# electrical_diagram.net
KiCad netlist of a schematic drawn in EAGLE
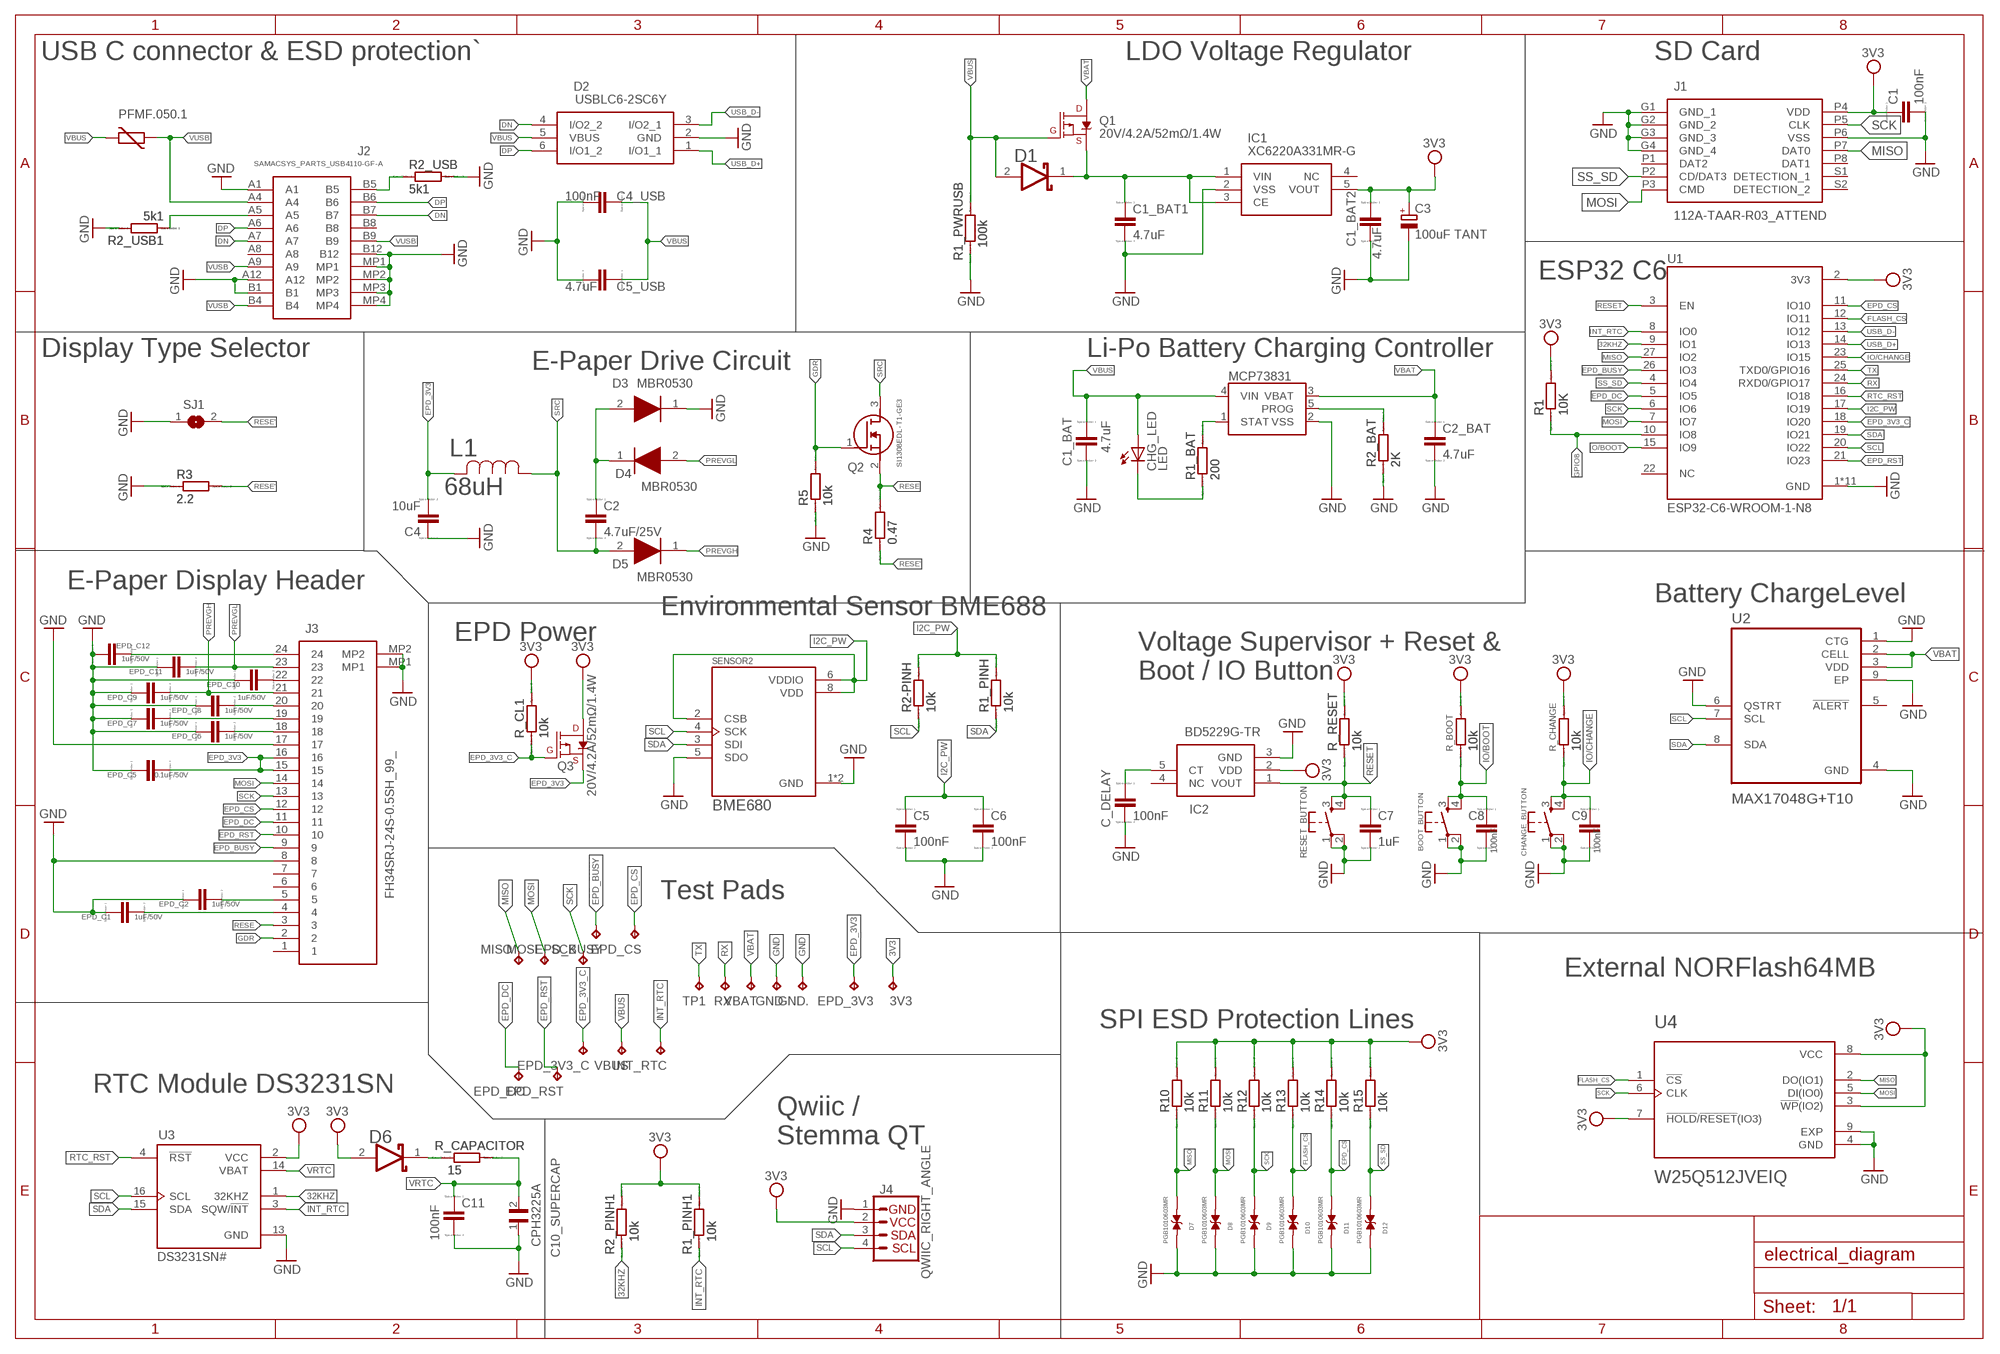
[diagram p0: schematic, sheet 1]

(export (version "E")
  (design (tool "Eeschema 10.0.6"))
  (components
    (comp (ref "3V3")
      (value "TP")
      (footprint "eagle-import:TP20R")
      (libsource (lib "eagle-import") (part "TP"))
    )
    (comp (ref "BOOT_BUTTON")
      (value "BUTTON_CUSYOMV1")
      (footprint "eagle-import:MYBUTTON")
      (libsource (lib "eagle-import") (part "BUTTON_CUSYOMV1"))
    )
    (comp (ref "C1")
      (value "100nF")
      (footprint "eagle-import:EAGLE-LTSPICE_C0402")
      (libsource (lib "eagle-import") (part "EAGLE-LTSPICE_C"))
    )
    (comp (ref "C1_BAT")
      (value "4.7uF")
      (footprint "eagle-import:EAGLE-LTSPICE_C0402")
      (libsource (lib "eagle-import") (part "EAGLE-LTSPICE_C"))
    )
    (comp (ref "C1_BAT1")
      (value "4.7uF")
      (footprint "eagle-import:EAGLE-LTSPICE_C0402")
      (libsource (lib "eagle-import") (part "EAGLE-LTSPICE_C"))
    )
    (comp (ref "C1_BAT2")
      (value "4.7uF")
      (footprint "eagle-import:EAGLE-LTSPICE_C0402")
      (libsource (lib "eagle-import") (part "EAGLE-LTSPICE_C"))
    )
    (comp (ref "C2")
      (value "4.7uF/25V")
      (footprint "eagle-import:EAGLE-LTSPICE_C0402")
      (libsource (lib "eagle-import") (part "EAGLE-LTSPICE_C"))
    )
    (comp (ref "C2_BAT")
      (value "4.7uF")
      (footprint "eagle-import:EAGLE-LTSPICE_C0402")
      (libsource (lib "eagle-import") (part "EAGLE-LTSPICE_C"))
    )
    (comp (ref "C3")
      (value "100uF TANT")
      (footprint "eagle-import:RCL_CT3528")
      (libsource (lib "eagle-import") (part "RCL_CPOL-EUCT3528"))
    )
    (comp (ref "C4")
      (value "10uF")
      (footprint "eagle-import:EAGLE-LTSPICE_C0402")
      (libsource (lib "eagle-import") (part "EAGLE-LTSPICE_C"))
    )
    (comp (ref "C4_USB")
      (value "100nF")
      (footprint "eagle-import:EAGLE-LTSPICE_C0402")
      (libsource (lib "eagle-import") (part "EAGLE-LTSPICE_C"))
    )
    (comp (ref "C5")
      (value "100nF")
      (footprint "eagle-import:ESP32_WROVER_EAGLE-LTSPICE_C0402")
      (libsource (lib "eagle-import") (part "ESP32_WROVER_EAGLE-LTSPICE_CC0402"))
    )
    (comp (ref "C5_USB")
      (value "4.7uF")
      (footprint "eagle-import:EAGLE-LTSPICE_C0402")
      (libsource (lib "eagle-import") (part "EAGLE-LTSPICE_C"))
    )
    (comp (ref "C6")
      (value "100nF")
      (footprint "eagle-import:ESP32_WROVER_EAGLE-LTSPICE_C0402")
      (libsource (lib "eagle-import") (part "ESP32_WROVER_EAGLE-LTSPICE_CC0402"))
    )
    (comp (ref "C7")
      (value "1uF")
      (footprint "eagle-import:ESP32_WROVER_EAGLE-LTSPICE_C0402")
      (libsource (lib "eagle-import") (part "ESP32_WROVER_EAGLE-LTSPICE_CC0402"))
    )
    (comp (ref "C8")
      (value "100nF")
      (footprint "eagle-import:ESP32_WROVER_EAGLE-LTSPICE_C0402")
      (libsource (lib "eagle-import") (part "ESP32_WROVER_EAGLE-LTSPICE_CC0402"))
    )
    (comp (ref "C9")
      (value "100nF")
      (footprint "eagle-import:ESP32_WROVER_EAGLE-LTSPICE_C0402")
      (libsource (lib "eagle-import") (part "ESP32_WROVER_EAGLE-LTSPICE_CC0402"))
    )
    (comp (ref "C10_SUPERCAP")
      (value "CPH3225A")
      (footprint "eagle-import:CAPCP3225X100N")
      (fields (field (name "MF") "Seiko Instruments"))
      (libsource (lib "eagle-import") (part "CPH3225A"))
    )
    (comp (ref "C11")
      (value "100nF")
      (footprint "eagle-import:ESP32_WROVER_EAGLE-LTSPICE_C0402")
      (libsource (lib "eagle-import") (part "ESP32_WROVER_EAGLE-LTSPICE_CC0402"))
    )
    (comp (ref "CHANGE_BUTTON")
      (value "BUTTON_CUSYOMV1")
      (footprint "eagle-import:MYBUTTON")
      (libsource (lib "eagle-import") (part "BUTTON_CUSYOMV1"))
    )
    (comp (ref "CHG_LED")
      (value "LED")
      (footprint "eagle-import:ADAFRUIT_CHIP-LED0603")
      (libsource (lib "eagle-import") (part "ADAFRUIT_LEDCHIP-LED0603"))
    )
    (comp (ref "C_DELAY")
      (value "100nF")
      (footprint "eagle-import:ESP32_WROVER_EAGLE-LTSPICE_C0402")
      (libsource (lib "eagle-import") (part "ESP32_WROVER_EAGLE-LTSPICE_CC0402"))
    )
    (comp (ref "D1")
      (value "ESP32_WROVER_AVX---SD0805S020S1R0_AVX_SD0805S020S1R0_0_0AVX_SD0805S020S1R0_0_0")
      (footprint "eagle-import:ESP32_WROVER_AVX---SD0805S020S1R0_AVX_SD0805S020S1R0_0")
      (fields
        (field (name "DIGIKEY_PART_NUMBER") "478-7800-1-ND")
        (field (name "MF") "AVX")
        (field (name "MOUSER_PART_NUMBER") "581-SD0805S020S1R0")
      )
      (libsource (lib "eagle-import") (part "ESP32_WROVER_AVX---SD0805S020S1R0_AVX_SD0805S020S1R0_0_0AVX_SD0805S020S1R0_0_0"))
    )
    (comp (ref "D2")
      (value "USBLC6-2SC6Y")
      (footprint "eagle-import:SOT95P280X145-6N")
      (fields (field (name "MF") "STMicroelectronics"))
      (libsource (lib "eagle-import") (part "USBLC6-2SC6Y"))
    )
    (comp (ref "D3")
      (value "MBR0530")
      (footprint "eagle-import:SOD3716X135N")
      (fields (field (name "MF") "ON Semiconductor"))
      (libsource (lib "eagle-import") (part "MBR0530"))
    )
    (comp (ref "D4")
      (value "MBR0530")
      (footprint "eagle-import:SOD3716X135N")
      (fields (field (name "MF") "ON Semiconductor"))
      (libsource (lib "eagle-import") (part "MBR0530"))
    )
    (comp (ref "D5")
      (value "MBR0530")
      (footprint "eagle-import:SOD3716X135N")
      (fields (field (name "MF") "ON Semiconductor"))
      (libsource (lib "eagle-import") (part "MBR0530"))
    )
    (comp (ref "D6")
      (value "ESP32_WROVER_AVX---SD0805S020S1R0_AVX_SD0805S020S1R0_0_0AVX_SD0805S020S1R0_0_0")
      (footprint "eagle-import:ESP32_WROVER_AVX---SD0805S020S1R0_AVX_SD0805S020S1R0_0")
      (fields
        (field (name "DIGIKEY_PART_NUMBER") "478-7800-1-ND")
        (field (name "MF") "AVX")
        (field (name "MOUSER_PART_NUMBER") "581-SD0805S020S1R0")
      )
      (libsource (lib "eagle-import") (part "ESP32_WROVER_AVX---SD0805S020S1R0_AVX_SD0805S020S1R0_0_0AVX_SD0805S020S1R0_0_0"))
    )
    (comp (ref "D7")
      (value "PGB1010603MR")
      (footprint "eagle-import:DIOC1608X36N")
      (fields (field (name "MF") "Littelfuse Inc."))
      (libsource (lib "eagle-import") (part "PGB1010603MR"))
    )
    (comp (ref "D8")
      (value "PGB1010603MR")
      (footprint "eagle-import:DIOC1608X36N")
      (fields (field (name "MF") "Littelfuse Inc."))
      (libsource (lib "eagle-import") (part "PGB1010603MR"))
    )
    (comp (ref "D9")
      (value "PGB1010603MR")
      (footprint "eagle-import:DIOC1608X36N")
      (fields (field (name "MF") "Littelfuse Inc."))
      (libsource (lib "eagle-import") (part "PGB1010603MR"))
    )
    (comp (ref "D10")
      (value "PGB1010603MR")
      (footprint "eagle-import:DIOC1608X36N")
      (fields (field (name "MF") "Littelfuse Inc."))
      (libsource (lib "eagle-import") (part "PGB1010603MR"))
    )
    (comp (ref "D11")
      (value "PGB1010603MR")
      (footprint "eagle-import:DIOC1608X36N")
      (fields (field (name "MF") "Littelfuse Inc."))
      (libsource (lib "eagle-import") (part "PGB1010603MR"))
    )
    (comp (ref "D12")
      (value "PGB1010603MR")
      (footprint "eagle-import:DIOC1608X36N")
      (fields (field (name "MF") "Littelfuse Inc."))
      (libsource (lib "eagle-import") (part "PGB1010603MR"))
    )
    (comp (ref "EPD_3V3")
      (value "TP")
      (footprint "eagle-import:TP20R")
      (libsource (lib "eagle-import") (part "TP"))
    )
    (comp (ref "EPD_3V3_C")
      (value "TP")
      (footprint "eagle-import:TP20R")
      (libsource (lib "eagle-import") (part "TP"))
    )
    (comp (ref "EPD_BUSY")
      (value "TP")
      (footprint "eagle-import:TP20R")
      (libsource (lib "eagle-import") (part "TP"))
    )
    (comp (ref "EPD_C1")
      (value "1uF/50V")
      (footprint "eagle-import:EAGLE-LTSPICE_C0402")
      (libsource (lib "eagle-import") (part "EAGLE-LTSPICE_C"))
    )
    (comp (ref "EPD_C2")
      (value "1uF/50V")
      (footprint "eagle-import:EAGLE-LTSPICE_C0402")
      (libsource (lib "eagle-import") (part "EAGLE-LTSPICE_C"))
    )
    (comp (ref "EPD_C5")
      (value "0.1uF/50V")
      (footprint "eagle-import:EAGLE-LTSPICE_C0402")
      (libsource (lib "eagle-import") (part "EAGLE-LTSPICE_C"))
    )
    (comp (ref "EPD_C6")
      (value "1uF/50V")
      (footprint "eagle-import:EAGLE-LTSPICE_C0402")
      (libsource (lib "eagle-import") (part "EAGLE-LTSPICE_C"))
    )
    (comp (ref "EPD_C7")
      (value "1uF/50V")
      (footprint "eagle-import:EAGLE-LTSPICE_C0402")
      (libsource (lib "eagle-import") (part "EAGLE-LTSPICE_C"))
    )
    (comp (ref "EPD_C8")
      (value "1uF/50V")
      (footprint "eagle-import:EAGLE-LTSPICE_C0402")
      (libsource (lib "eagle-import") (part "EAGLE-LTSPICE_C"))
    )
    (comp (ref "EPD_C9")
      (value "1uF/50V")
      (footprint "eagle-import:EAGLE-LTSPICE_C0402")
      (libsource (lib "eagle-import") (part "EAGLE-LTSPICE_C"))
    )
    (comp (ref "EPD_C10")
      (value "1uF/50V")
      (footprint "eagle-import:EAGLE-LTSPICE_C0402")
      (libsource (lib "eagle-import") (part "EAGLE-LTSPICE_C"))
    )
    (comp (ref "EPD_C11")
      (value "1uF/50V")
      (footprint "eagle-import:EAGLE-LTSPICE_C0402")
      (libsource (lib "eagle-import") (part "EAGLE-LTSPICE_C"))
    )
    (comp (ref "EPD_C12")
      (value "1uF/50V")
      (footprint "eagle-import:EAGLE-LTSPICE_C0402")
      (libsource (lib "eagle-import") (part "EAGLE-LTSPICE_C"))
    )
    (comp (ref "EPD_CS")
      (value "TP")
      (footprint "eagle-import:TP20R")
      (libsource (lib "eagle-import") (part "TP"))
    )
    (comp (ref "EPD_DC")
      (value "TP")
      (footprint "eagle-import:TP20R")
      (libsource (lib "eagle-import") (part "TP"))
    )
    (comp (ref "EPD_RST")
      (value "TP")
      (footprint "eagle-import:TP20R")
      (libsource (lib "eagle-import") (part "TP"))
    )
    (comp (ref "GND")
      (value "TP")
      (footprint "eagle-import:TP20R")
      (libsource (lib "eagle-import") (part "TP"))
    )
    (comp (ref "GND.")
      (value "TP")
      (footprint "eagle-import:TP20R")
      (libsource (lib "eagle-import") (part "TP"))
    )
    (comp (ref "IC1")
      (value "XC6220A331MR-G")
      (footprint "eagle-import:SOT95P280X120-5N")
      (fields (field (name "MOUSER_PART_NUMBER") "865-XC6220A331MR-G"))
      (libsource (lib "eagle-import") (part "XC6220A331MR-G"))
    )
    (comp (ref "IC2")
      (value "BD5229G-TR")
      (footprint "eagle-import:SOT95P280X125-5N")
      (fields (field (name "MOUSER_PART_NUMBER") "755-BD5229G-TR"))
      (libsource (lib "eagle-import") (part "BD5229G-TR"))
    )
    (comp (ref "INT_RTC")
      (value "TP")
      (footprint "eagle-import:TP20R")
      (libsource (lib "eagle-import") (part "TP"))
    )
    (comp (ref "J1")
      (value "112A-TAAR-R03_ATTEND")
      (footprint "eagle-import:112ATAARR03ATTEND")
      (fields (field (name "MANUFACTURER_PART_NUMBER") "112A-TAAR-R03 ATTEND"))
      (libsource (lib "eagle-import") (part "112A-TAAR-R03_ATTEND"))
    )
    (comp (ref "J2")
      (value "SAMACSYS_PARTS_USB4110-GF-A")
      (footprint "eagle-import:SAMACSYS_PARTS_USB4110GFA")
      (fields
        (field (name "MANUFACTURER_PART_NUMBER") "USB4110-GF-A")
        (field (name "MOUSER_PART_NUMBER") "640-USB4110-GF-A")
      )
      (libsource (lib "eagle-import") (part "SAMACSYS_PARTS_USB4110-GF-A"))
    )
    (comp (ref "J3")
      (value "FH34SRJ-24S-0.5SH_99_")
      (footprint "eagle-import:FH34SRJ24S05SH99")
      (fields
        (field (name "MANUFACTURER_PART_NUMBER") "FH34SRJ-24S-0.5SH(99)")
        (field (name "MOUSER_PART_NUMBER") "798-FH34SRJ24S05SH99")
      )
      (libsource (lib "eagle-import") (part "FH34SRJ-24S-0.5SH_99_"))
    )
    (comp (ref "J4")
      (value "QWIIC_RIGHT_ANGLE")
      (footprint "eagle-import:JST04_1MM_RA")
      (libsource (lib "eagle-import") (part "QWIIC_CONNECTORJS-1MM"))
    )
    (comp (ref "L1")
      (value "68uH")
      (footprint "eagle-import:IND_4828-WE-TPC_WRE")
      (fields
        (field (name "MANUFACTURER_PART_NUMBER") "744043680")
        (field (name "COPYRIGHT") "Copyright (C) 2024 Ultra Librarian. All rights reserved.")
      )
      (libsource (lib "eagle-import") (part "744043680IND_4828-WE-TPC_WRE"))
    )
    (comp (ref "MCP73831")
      (value "ESP32_WROVER_SPARKFUN-IC-POWER_MCP73831")
      (footprint "eagle-import:ESP32_WROVER_SPARKFUN-IC-POWER_SOT23-5")
      (libsource (lib "eagle-import") (part "ESP32_WROVER_SPARKFUN-IC-POWER_MCP73831"))
    )
    (comp (ref "MISO")
      (value "TP")
      (footprint "eagle-import:TP20R")
      (libsource (lib "eagle-import") (part "TP"))
    )
    (comp (ref "MOSI")
      (value "TP")
      (footprint "eagle-import:TP20R")
      (libsource (lib "eagle-import") (part "TP"))
    )
    (comp (ref "PFMF.050.1")
      (value "ESP32C6_VARISTORCN1812")
      (footprint "eagle-import:ESP32C6_VARISTOR_CT_CN1812")
      (libsource (lib "eagle-import") (part "ESP32C6_VARISTORCN1812"))
    )
    (comp (ref "Q1")
      (value "20V/4.2A/52mΩ/1.4W")
      (footprint "eagle-import:ESP32_WROVER_SPARKFUN-DISCRETESEMI_SOT23-3")
      (libsource (lib "eagle-import") (part "ESP32_WROVER_SPARKFUN-DISCRETESEMI_MOSFET_PCH-DMG2305UX-7"))
    )
    (comp (ref "Q2")
      (value "SI1308EDL-T1-GE3")
      (footprint "eagle-import:SOT65P210X110-3N")
      (fields (field (name "MF") "Vishay Siliconix"))
      (libsource (lib "eagle-import") (part "SI1308EDL-T1-GE3"))
    )
    (comp (ref "Q3")
      (value "20V/4.2A/52mΩ/1.4W")
      (footprint "eagle-import:ESP32_WROVER_SPARKFUN-DISCRETESEMI_SOT23-3")
      (libsource (lib "eagle-import") (part "ESP32_WROVER_SPARKFUN-DISCRETESEMI_MOSFET_PCH-DMG2305UX-7"))
    )
    (comp (ref "R1")
      (value "10K")
      (footprint "eagle-import:ESP32_WROVER_EAGLE-LTSPICE_R0402")
      (libsource (lib "eagle-import") (part "ESP32_WROVER_EAGLE-LTSPICE_R"))
    )
    (comp (ref "R1_BAT")
      (value "200")
      (footprint "eagle-import:ESP32_WROVER_EAGLE-LTSPICE_R0402")
      (libsource (lib "eagle-import") (part "ESP32_WROVER_EAGLE-LTSPICE_R"))
    )
    (comp (ref "R1_PINH")
      (value "10k")
      (footprint "eagle-import:ESP32_WROVER_EAGLE-LTSPICE_R0402")
      (libsource (lib "eagle-import") (part "ESP32_WROVER_EAGLE-LTSPICE_R"))
    )
    (comp (ref "R1_PINH1")
      (value "10k")
      (footprint "eagle-import:ESP32_WROVER_EAGLE-LTSPICE_R0402")
      (libsource (lib "eagle-import") (part "ESP32_WROVER_EAGLE-LTSPICE_R"))
    )
    (comp (ref "R1_PWRUSB")
      (value "100k")
      (footprint "eagle-import:ESP32_WROVER_EAGLE-LTSPICE_R0402")
      (libsource (lib "eagle-import") (part "ESP32_WROVER_EAGLE-LTSPICE_R"))
    )
    (comp (ref "R2-PINH")
      (value "10k")
      (footprint "eagle-import:ESP32_WROVER_EAGLE-LTSPICE_R0402")
      (libsource (lib "eagle-import") (part "ESP32_WROVER_EAGLE-LTSPICE_R"))
    )
    (comp (ref "R2_BAT")
      (value "2K")
      (footprint "eagle-import:ESP32_WROVER_EAGLE-LTSPICE_R0402")
      (libsource (lib "eagle-import") (part "ESP32_WROVER_EAGLE-LTSPICE_R"))
    )
    (comp (ref "R2_PINH1")
      (value "10k")
      (footprint "eagle-import:ESP32_WROVER_EAGLE-LTSPICE_R0402")
      (libsource (lib "eagle-import") (part "ESP32_WROVER_EAGLE-LTSPICE_R"))
    )
    (comp (ref "R2_USB")
      (value "5k1")
      (footprint "eagle-import:ESP32_WROVER_EAGLE-LTSPICE_R0402")
      (libsource (lib "eagle-import") (part "ESP32_WROVER_EAGLE-LTSPICE_R"))
    )
    (comp (ref "R2_USB1")
      (value "5k1")
      (footprint "eagle-import:ESP32_WROVER_EAGLE-LTSPICE_R0402")
      (libsource (lib "eagle-import") (part "ESP32_WROVER_EAGLE-LTSPICE_R"))
    )
    (comp (ref "R3")
      (value "2.2")
      (footprint "eagle-import:ESP32_WROVER_EAGLE-LTSPICE_R0402")
      (libsource (lib "eagle-import") (part "ESP32_WROVER_EAGLE-LTSPICE_R"))
    )
    (comp (ref "R4")
      (value "0.47")
      (footprint "eagle-import:ESP32_WROVER_EAGLE-LTSPICE_R0402")
      (libsource (lib "eagle-import") (part "ESP32_WROVER_EAGLE-LTSPICE_R"))
    )
    (comp (ref "R5")
      (value "10k")
      (footprint "eagle-import:ESP32_WROVER_EAGLE-LTSPICE_R0402")
      (libsource (lib "eagle-import") (part "ESP32_WROVER_EAGLE-LTSPICE_R"))
    )
    (comp (ref "R10")
      (value "10k")
      (footprint "eagle-import:ESP32_WROVER_EAGLE-LTSPICE_R0402")
      (libsource (lib "eagle-import") (part "ESP32_WROVER_EAGLE-LTSPICE_R"))
    )
    (comp (ref "R11")
      (value "10k")
      (footprint "eagle-import:ESP32_WROVER_EAGLE-LTSPICE_R0402")
      (libsource (lib "eagle-import") (part "ESP32_WROVER_EAGLE-LTSPICE_R"))
    )
    (comp (ref "R12")
      (value "10k")
      (footprint "eagle-import:ESP32_WROVER_EAGLE-LTSPICE_R0402")
      (libsource (lib "eagle-import") (part "ESP32_WROVER_EAGLE-LTSPICE_R"))
    )
    (comp (ref "R13")
      (value "10k")
      (footprint "eagle-import:ESP32_WROVER_EAGLE-LTSPICE_R0402")
      (libsource (lib "eagle-import") (part "ESP32_WROVER_EAGLE-LTSPICE_R"))
    )
    (comp (ref "R14")
      (value "10k")
      (footprint "eagle-import:ESP32_WROVER_EAGLE-LTSPICE_R0402")
      (libsource (lib "eagle-import") (part "ESP32_WROVER_EAGLE-LTSPICE_R"))
    )
    (comp (ref "R15")
      (value "10k")
      (footprint "eagle-import:ESP32_WROVER_EAGLE-LTSPICE_R0402")
      (libsource (lib "eagle-import") (part "ESP32_WROVER_EAGLE-LTSPICE_R"))
    )
    (comp (ref "RESET_BUTTON")
      (value "BUTTON_CUSYOMV1")
      (footprint "eagle-import:MYBUTTON")
      (libsource (lib "eagle-import") (part "BUTTON_CUSYOMV1"))
    )
    (comp (ref "RX")
      (value "TP")
      (footprint "eagle-import:TP20R")
      (libsource (lib "eagle-import") (part "TP"))
    )
    (comp (ref "R_BOOT")
      (value "10k")
      (footprint "eagle-import:ESP32_WROVER_EAGLE-LTSPICE_R0402")
      (libsource (lib "eagle-import") (part "ESP32_WROVER_EAGLE-LTSPICE_R"))
    )
    (comp (ref "R_CAPACITOR")
      (value "15")
      (footprint "eagle-import:ESP32_WROVER_EAGLE-LTSPICE_R0402")
      (libsource (lib "eagle-import") (part "ESP32_WROVER_EAGLE-LTSPICE_R"))
    )
    (comp (ref "R_CHANGE")
      (value "10k")
      (footprint "eagle-import:ESP32_WROVER_EAGLE-LTSPICE_R0402")
      (libsource (lib "eagle-import") (part "ESP32_WROVER_EAGLE-LTSPICE_R"))
    )
    (comp (ref "R_CL1")
      (value "10k")
      (footprint "eagle-import:ESP32_WROVER_EAGLE-LTSPICE_R0402")
      (libsource (lib "eagle-import") (part "ESP32_WROVER_EAGLE-LTSPICE_R"))
    )
    (comp (ref "R_RESET")
      (value "10k")
      (footprint "eagle-import:ESP32_WROVER_EAGLE-LTSPICE_R0402")
      (libsource (lib "eagle-import") (part "ESP32_WROVER_EAGLE-LTSPICE_R"))
    )
    (comp (ref "SCK")
      (value "TP")
      (footprint "eagle-import:TP20R")
      (libsource (lib "eagle-import") (part "TP"))
    )
    (comp (ref "SENSOR2")
      (value "BME680")
      (footprint "eagle-import:ESP32_WROVER_BME680_PSON80P300X300X100-8N")
      (fields (field (name "MF") "Bosch Sensortec"))
      (libsource (lib "eagle-import") (part "ESP32_WROVER_BME680_BME680"))
    )
    (comp (ref "SJ1") (value "-") (footprint "eagle-import:SJ") (libsource (lib "eagle-import") (part "SJ")))
    (comp (ref "TP1")
      (value "TP")
      (footprint "eagle-import:TP20R")
      (libsource (lib "eagle-import") (part "TP"))
    )
    (comp (ref "U1")
      (value "ESP32-C6-WROOM-1-N8")
      (footprint "eagle-import:XCVR_ESP32-C6-WROOM-1-N8")
      (fields (field (name "MF") "Espressif Systems"))
      (libsource (lib "eagle-import") (part "ESP32-C6-WROOM-1-N8"))
    )
    (comp (ref "U2")
      (value "MAX17048G+T10")
      (footprint "eagle-import:SON50P200X200X80-9N")
      (fields (field (name "MF") "Analog Devices"))
      (libsource (lib "eagle-import") (part "MAX17048G+T10"))
    )
    (comp (ref "U3")
      (value "DS3231SN#")
      (footprint "eagle-import:SOIC127P1032X265-16N")
      (fields (field (name "MF") "Analog Devices"))
      (libsource (lib "eagle-import") (part "DS3231SN#"))
    )
    (comp (ref "U4")
      (value "W25Q512JVEIQ")
      (footprint "eagle-import:SON127P600X800X80-9N")
      (fields (field (name "MF") "Winbond Electronics"))
      (libsource (lib "eagle-import") (part "W25Q512JVEIQ"))
    )
    (comp (ref "VBAT")
      (value "TP")
      (footprint "eagle-import:TP20R")
      (libsource (lib "eagle-import") (part "TP"))
    )
    (comp (ref "VBUS")
      (value "TP")
      (footprint "eagle-import:TP20R")
      (libsource (lib "eagle-import") (part "TP"))
    )
  )
  (nets
    (net (code "1") (name "3V3") (class "Default")
      (node (ref "3V3") (pin "TP") (pinfunction "TP_TP") (pintype "input"))
      (node (ref "C1") (pin "1") (pinfunction "1_1") (pintype "passive"))
      (node (ref "C1_BAT2") (pin "1") (pinfunction "1_1") (pintype "passive"))
      (node (ref "C3") (pin "+") (pinfunction "+_+") (pintype "passive"))
      (node (ref "D6") (pin "2") (pinfunction "ANODE_2") (pintype "bidirectional"))
      (node (ref "IC1") (pin "5") (pinfunction "VOUT_5") (pintype "bidirectional"))
      (node (ref "IC2") (pin "2") (pinfunction "VDD_2") (pintype "bidirectional"))
      (node (ref "J1") (pin "P4") (pinfunction "VDD_P4") (pintype "bidirectional"))
      (node (ref "J4") (pin "2") (pinfunction "2_2") (pintype "power_in"))
      (node (ref "Q3") (pin "3") (pinfunction "D_3") (pintype "bidirectional"))
      (node (ref "R1") (pin "2") (pinfunction "2_2") (pintype "passive"))
      (node (ref "R10") (pin "2") (pinfunction "2_2") (pintype "passive"))
      (node (ref "R11") (pin "2") (pinfunction "2_2") (pintype "passive"))
      (node (ref "R12") (pin "2") (pinfunction "2_2") (pintype "passive"))
      (node (ref "R13") (pin "2") (pinfunction "2_2") (pintype "passive"))
      (node (ref "R14") (pin "2") (pinfunction "2_2") (pintype "passive"))
      (node (ref "R15") (pin "2") (pinfunction "2_2") (pintype "passive"))
      (node (ref "R1_PINH1") (pin "2") (pinfunction "2_2") (pintype "passive"))
      (node (ref "R2_PINH1") (pin "2") (pinfunction "2_2") (pintype "passive"))
      (node (ref "R_BOOT") (pin "2") (pinfunction "2_2") (pintype "passive"))
      (node (ref "R_CHANGE") (pin "2") (pinfunction "2_2") (pintype "passive"))
      (node (ref "R_CL1") (pin "2") (pinfunction "2_2") (pintype "passive"))
      (node (ref "R_RESET") (pin "2") (pinfunction "2_2") (pintype "passive"))
      (node (ref "U1") (pin "2") (pinfunction "3V3_2") (pintype "power_in"))
      (node (ref "U3") (pin "2") (pinfunction "VCC_2") (pintype "power_in"))
      (node (ref "U4") (pin "3") (pinfunction "~{WP}(IO2)_3") (pintype "bidirectional"))
      (node (ref "U4") (pin "7") (pinfunction "~{HOLD}/~{RESET}(IO3)_7") (pintype "bidirectional"))
      (node (ref "U4") (pin "8") (pinfunction "VCC_8") (pintype "power_in"))
    )
    (net (code "2") (name "32KHZ") (class "Default")
      (node (ref "R2_PINH1") (pin "1") (pinfunction "1_1") (pintype "passive"))
      (node (ref "U1") (pin "9") (pinfunction "IO1_9") (pintype "bidirectional"))
      (node (ref "U3") (pin "1") (pinfunction "32KHZ_1") (pintype "output"))
    )
    (net (code "3") (name "DN") (class "Default")
      (node (ref "D2") (pin "4") (pinfunction "I/O2_2_4") (pintype "bidirectional"))
      (node (ref "J2") (pin "A7") (pinfunction "A7_A7") (pintype "bidirectional"))
      (node (ref "J2") (pin "B7") (pinfunction "B7_B7") (pintype "bidirectional"))
    )
    (net (code "4") (name "DP") (class "Default")
      (node (ref "D2") (pin "6") (pinfunction "I/O1_2_6") (pintype "bidirectional"))
      (node (ref "J2") (pin "A6") (pinfunction "A6_A6") (pintype "bidirectional"))
      (node (ref "J2") (pin "B6") (pinfunction "B6_B6") (pintype "bidirectional"))
    )
    (net (code "5") (name "EPD_3V3") (class "Default")
      (node (ref "C4") (pin "2") (pinfunction "2_2") (pintype "passive"))
      (node (ref "EPD_3V3") (pin "TP") (pinfunction "TP_TP") (pintype "input"))
      (node (ref "EPD_C5") (pin "2") (pinfunction "2_2") (pintype "passive"))
      (node (ref "J3") (pin "15") (pinfunction "15_15") (pintype "bidirectional"))
      (node (ref "J3") (pin "16") (pinfunction "16_16") (pintype "bidirectional"))
      (node (ref "L1") (pin "2") (pinfunction "2_2") (pintype "passive"))
      (node (ref "Q3") (pin "2") (pinfunction "S_2") (pintype "bidirectional"))
    )
    (net (code "6") (name "EPD_3V3_C") (class "Default")
      (node (ref "EPD_3V3_C") (pin "TP") (pinfunction "TP_TP") (pintype "input"))
      (node (ref "Q3") (pin "1") (pinfunction "G_1") (pintype "bidirectional"))
      (node (ref "R_CL1") (pin "1") (pinfunction "1_1") (pintype "passive"))
      (node (ref "U1") (pin "18") (pinfunction "IO20_18") (pintype "bidirectional"))
    )
    (net (code "7") (name "EPD_BUSY") (class "Default")
      (node (ref "EPD_BUSY") (pin "TP") (pinfunction "TP_TP") (pintype "input"))
      (node (ref "J3") (pin "9") (pinfunction "9_9") (pintype "bidirectional"))
      (node (ref "U1") (pin "26") (pinfunction "IO3_26") (pintype "bidirectional"))
    )
    (net (code "8") (name "EPD_CS") (class "Default")
      (node (ref "D11") (pin "1") (pinfunction "1_1") (pintype "passive"))
      (node (ref "EPD_CS") (pin "TP") (pinfunction "TP_TP") (pintype "input"))
      (node (ref "J3") (pin "12") (pinfunction "12_12") (pintype "bidirectional"))
      (node (ref "R14") (pin "1") (pinfunction "1_1") (pintype "passive"))
      (node (ref "U1") (pin "11") (pinfunction "IO10_11") (pintype "bidirectional"))
    )
    (net (code "9") (name "EPD_DC") (class "Default")
      (node (ref "EPD_DC") (pin "TP") (pinfunction "TP_TP") (pintype "input"))
      (node (ref "J3") (pin "11") (pinfunction "11_11") (pintype "bidirectional"))
      (node (ref "U1") (pin "5") (pinfunction "IO5_5") (pintype "bidirectional"))
    )
    (net (code "10") (name "EPD_RST") (class "Default")
      (node (ref "EPD_RST") (pin "TP") (pinfunction "TP_TP") (pintype "input"))
      (node (ref "J3") (pin "10") (pinfunction "10_10") (pintype "bidirectional"))
      (node (ref "U1") (pin "21") (pinfunction "IO23_21") (pintype "bidirectional"))
    )
    (net (code "11") (name "FLASH_CS") (class "Default")
      (node (ref "D10") (pin "1") (pinfunction "1_1") (pintype "passive"))
      (node (ref "R13") (pin "1") (pinfunction "1_1") (pintype "passive"))
      (node (ref "U1") (pin "12") (pinfunction "IO11_12") (pintype "bidirectional"))
      (node (ref "U4") (pin "1") (pinfunction "~{CS}_1") (pintype "input"))
    )
    (net (code "12") (name "GDR") (class "Default")
      (node (ref "J3") (pin "2") (pinfunction "2_2") (pintype "bidirectional"))
      (node (ref "Q2") (pin "1") (pinfunction "G_1") (pintype "bidirectional"))
      (node (ref "R5") (pin "2") (pinfunction "2_2") (pintype "passive"))
    )
    (net (code "13") (name "GND") (class "Default")
      (node (ref "BOOT_BUTTON") (pin "1") (pinfunction "1_1") (pintype "passive"))
      (node (ref "BOOT_BUTTON") (pin "2") (pinfunction "2_2") (pintype "passive"))
      (node (ref "C1") (pin "2") (pinfunction "2_2") (pintype "passive"))
      (node (ref "C10_SUPERCAP") (pin "1") (pinfunction "1_1") (pintype "passive"))
      (node (ref "C11") (pin "2") (pinfunction "2_2") (pintype "passive"))
      (node (ref "C1_BAT") (pin "2") (pinfunction "2_2") (pintype "passive"))
      (node (ref "C1_BAT1") (pin "2") (pinfunction "2_2") (pintype "passive"))
      (node (ref "C1_BAT2") (pin "2") (pinfunction "2_2") (pintype "passive"))
      (node (ref "C2_BAT") (pin "2") (pinfunction "2_2") (pintype "passive"))
      (node (ref "C3") (pin "-") (pinfunction "-_-") (pintype "passive"))
      (node (ref "C4") (pin "1") (pinfunction "1_1") (pintype "passive"))
      (node (ref "C4_USB") (pin "2") (pinfunction "2_2") (pintype "passive"))
      (node (ref "C5") (pin "2") (pinfunction "2_2") (pintype "passive"))
      (node (ref "C5_USB") (pin "2") (pinfunction "2_2") (pintype "passive"))
      (node (ref "C6") (pin "2") (pinfunction "2_2") (pintype "passive"))
      (node (ref "C7") (pin "2") (pinfunction "2_2") (pintype "passive"))
      (node (ref "C8") (pin "2") (pinfunction "2_2") (pintype "passive"))
      (node (ref "C9") (pin "2") (pinfunction "2_2") (pintype "passive"))
      (node (ref "CHANGE_BUTTON") (pin "1") (pinfunction "1_1") (pintype "passive"))
      (node (ref "CHANGE_BUTTON") (pin "2") (pinfunction "2_2") (pintype "passive"))
      (node (ref "C_DELAY") (pin "2") (pinfunction "2_2") (pintype "passive"))
      (node (ref "D10") (pin "2") (pinfunction "2_2") (pintype "passive"))
      (node (ref "D11") (pin "2") (pinfunction "2_2") (pintype "passive"))
      (node (ref "D12") (pin "2") (pinfunction "2_2") (pintype "passive"))
      (node (ref "D2") (pin "2") (pinfunction "GND_2") (pintype "bidirectional"))
      (node (ref "D3") (pin "1") (pinfunction "K_1") (pintype "bidirectional"))
      (node (ref "D7") (pin "2") (pinfunction "2_2") (pintype "passive"))
      (node (ref "D8") (pin "2") (pinfunction "2_2") (pintype "passive"))
      (node (ref "D9") (pin "2") (pinfunction "2_2") (pintype "passive"))
      (node (ref "EPD_C1") (pin "1") (pinfunction "1_1") (pintype "passive"))
      (node (ref "EPD_C10") (pin "1") (pinfunction "1_1") (pintype "passive"))
      (node (ref "EPD_C11") (pin "1") (pinfunction "1_1") (pintype "passive"))
      (node (ref "EPD_C12") (pin "1") (pinfunction "1_1") (pintype "passive"))
      (node (ref "EPD_C2") (pin "1") (pinfunction "1_1") (pintype "passive"))
      (node (ref "EPD_C5") (pin "1") (pinfunction "1_1") (pintype "passive"))
      (node (ref "EPD_C6") (pin "1") (pinfunction "1_1") (pintype "passive"))
      (node (ref "EPD_C7") (pin "1") (pinfunction "1_1") (pintype "passive"))
      (node (ref "EPD_C8") (pin "1") (pinfunction "1_1") (pintype "passive"))
      (node (ref "EPD_C9") (pin "1") (pinfunction "1_1") (pintype "passive"))
      (node (ref "GND") (pin "TP") (pinfunction "TP_TP") (pintype "input"))
      (node (ref "GND.") (pin "TP") (pinfunction "TP_TP") (pintype "input"))
      (node (ref "IC1") (pin "2") (pinfunction "VSS_2") (pintype "bidirectional"))
      (node (ref "IC2") (pin "3") (pinfunction "GND_3") (pintype "bidirectional"))
      (node (ref "J1") (pin "G1") (pinfunction "GND_1_G1") (pintype "bidirectional"))
      (node (ref "J1") (pin "G2") (pinfunction "GND_2_G2") (pintype "bidirectional"))
      (node (ref "J1") (pin "G3") (pinfunction "GND_3_G3") (pintype "bidirectional"))
      (node (ref "J1") (pin "G4") (pinfunction "GND_4_G4") (pintype "bidirectional"))
      (node (ref "J1") (pin "P6") (pinfunction "VSS_P6") (pintype "bidirectional"))
      (node (ref "J2") (pin "A1") (pinfunction "A1_A1") (pintype "bidirectional"))
      (node (ref "J2") (pin "A12") (pinfunction "A12_A12") (pintype "bidirectional"))
      (node (ref "J2") (pin "B1") (pinfunction "B1_B1") (pintype "bidirectional"))
      (node (ref "J2") (pin "B12") (pinfunction "B12_B12") (pintype "bidirectional"))
      (node (ref "J2") (pin "MP1") (pinfunction "MP1_MP1") (pintype "bidirectional"))
      (node (ref "J2") (pin "MP2") (pinfunction "MP2_MP2") (pintype "bidirectional"))
      (node (ref "J2") (pin "MP3") (pinfunction "MP3_MP3") (pintype "bidirectional"))
      (node (ref "J2") (pin "MP4") (pinfunction "MP4_MP4") (pintype "bidirectional"))
      (node (ref "J3") (pin "17") (pinfunction "17_17") (pintype "bidirectional"))
      (node (ref "J3") (pin "8") (pinfunction "8_8") (pintype "bidirectional"))
      (node (ref "J3") (pin "MP1") (pinfunction "MP1_MP1") (pintype "bidirectional"))
      (node (ref "J3") (pin "MP2") (pinfunction "MP2_MP2") (pintype "bidirectional"))
      (node (ref "J4") (pin "1") (pinfunction "1_1") (pintype "power_in"))
      (node (ref "MCP73831") (pin "2") (pinfunction "VSS_2") (pintype "power_in"))
      (node (ref "R1_PWRUSB") (pin "1") (pinfunction "1_1") (pintype "passive"))
      (node (ref "R2_BAT") (pin "1") (pinfunction "1_1") (pintype "passive"))
      (node (ref "R2_USB") (pin "2") (pinfunction "2_2") (pintype "passive"))
      (node (ref "R2_USB1") (pin "2") (pinfunction "2_2") (pintype "passive"))
      (node (ref "R3") (pin "1") (pinfunction "1_1") (pintype "passive"))
      (node (ref "R5") (pin "1") (pinfunction "1_1") (pintype "passive"))
      (node (ref "RESET_BUTTON") (pin "1") (pinfunction "1_1") (pintype "passive"))
      (node (ref "RESET_BUTTON") (pin "2") (pinfunction "2_2") (pintype "passive"))
      (node (ref "SENSOR2") (pin "1") (pinfunction "GND_1") (pintype "power_in"))
      (node (ref "SENSOR2") (pin "5") (pinfunction "SDO_5") (pintype "bidirectional"))
      (node (ref "SENSOR2") (pin "7") (pinfunction "GND_7") (pintype "power_in"))
      (node (ref "SJ1") (pin "1") (pinfunction "1_1") (pintype "passive"))
      (node (ref "U1") (pin "1") (pinfunction "GND_1") (pintype "power_in"))
      (node (ref "U1") (pin "28") (pinfunction "GND_28") (pintype "power_in"))
      (node (ref "U1") (pin "29_1") (pinfunction "GND_29_1") (pintype "power_in"))
      (node (ref "U1") (pin "29_2") (pinfunction "GND_29_2") (pintype "power_in"))
      (node (ref "U1") (pin "29_3") (pinfunction "GND_29_3") (pintype "power_in"))
      (node (ref "U1") (pin "29_4") (pinfunction "GND_29_4") (pintype "power_in"))
      (node (ref "U1") (pin "29_5") (pinfunction "GND_29_5") (pintype "power_in"))
      (node (ref "U1") (pin "29_6") (pinfunction "GND_29_6") (pintype "power_in"))
      (node (ref "U1") (pin "29_7") (pinfunction "GND_29_7") (pintype "power_in"))
      (node (ref "U1") (pin "29_8") (pinfunction "GND_29_8") (pintype "power_in"))
      (node (ref "U1") (pin "29_9") (pinfunction "GND_29_9") (pintype "power_in"))
      (node (ref "U2") (pin "1") (pinfunction "CTG_1") (pintype "power_in"))
      (node (ref "U2") (pin "4") (pinfunction "GND_4") (pintype "power_in"))
      (node (ref "U2") (pin "6") (pinfunction "QSTRT_6") (pintype "input"))
      (node (ref "U2") (pin "9") (pinfunction "EP_9") (pintype "power_in"))
      (node (ref "U3") (pin "13") (pinfunction "GND_13") (pintype "power_in"))
      (node (ref "U4") (pin "4") (pinfunction "GND_4") (pintype "power_in"))
      (node (ref "U4") (pin "9") (pinfunction "EXP_9") (pintype "passive"))
    )
    (net (code "14") (name "GPIO8") (class "Default")
      (node (ref "R1") (pin "1") (pinfunction "1_1") (pintype "passive"))
      (node (ref "U1") (pin "10") (pinfunction "IO8_10") (pintype "bidirectional"))
    )
    (net (code "15") (name "I2C_PW") (class "Default")
      (node (ref "C5") (pin "1") (pinfunction "1_1") (pintype "passive"))
      (node (ref "C6") (pin "1") (pinfunction "1_1") (pintype "passive"))
      (node (ref "R1_PINH") (pin "2") (pinfunction "2_2") (pintype "passive"))
      (node (ref "R2-PINH") (pin "2") (pinfunction "2_2") (pintype "passive"))
      (node (ref "SENSOR2") (pin "2") (pinfunction "CSB_2") (pintype "input"))
      (node (ref "SENSOR2") (pin "6") (pinfunction "VDDIO_6") (pintype "power_in"))
      (node (ref "SENSOR2") (pin "8") (pinfunction "VDD_8") (pintype "power_in"))
      (node (ref "U1") (pin "17") (pinfunction "IO19_17") (pintype "bidirectional"))
    )
    (net (code "16") (name "INT_RTC") (class "Default")
      (node (ref "INT_RTC") (pin "TP") (pinfunction "TP_TP") (pintype "input"))
      (node (ref "R1_PINH1") (pin "1") (pinfunction "1_1") (pintype "passive"))
      (node (ref "U1") (pin "8") (pinfunction "IO0_8") (pintype "bidirectional"))
      (node (ref "U3") (pin "3") (pinfunction "SQW/~{INT}_3") (pintype "output"))
    )
    (net (code "17") (name "IO{slash}BOOT") (class "Default")
      (node (ref "BOOT_BUTTON") (pin "3") (pinfunction "3_3") (pintype "passive"))
      (node (ref "BOOT_BUTTON") (pin "4") (pinfunction "4_4") (pintype "passive"))
      (node (ref "C8") (pin "1") (pinfunction "1_1") (pintype "passive"))
      (node (ref "R_BOOT") (pin "1") (pinfunction "1_1") (pintype "passive"))
      (node (ref "U1") (pin "15") (pinfunction "IO9_15") (pintype "bidirectional"))
    )
    (net (code "18") (name "IO{slash}CHANGE") (class "Default")
      (node (ref "C9") (pin "1") (pinfunction "1_1") (pintype "passive"))
      (node (ref "CHANGE_BUTTON") (pin "3") (pinfunction "3_3") (pintype "passive"))
      (node (ref "CHANGE_BUTTON") (pin "4") (pinfunction "4_4") (pintype "passive"))
      (node (ref "R_CHANGE") (pin "1") (pinfunction "1_1") (pintype "passive"))
      (node (ref "U1") (pin "23") (pinfunction "IO15_23") (pintype "bidirectional"))
    )
    (net (code "19") (name "MISO") (class "Default")
      (node (ref "D7") (pin "1") (pinfunction "1_1") (pintype "passive"))
      (node (ref "J1") (pin "P7") (pinfunction "DAT0_P7") (pintype "bidirectional"))
      (node (ref "MISO") (pin "TP") (pinfunction "TP_TP") (pintype "input"))
      (node (ref "R10") (pin "1") (pinfunction "1_1") (pintype "passive"))
      (node (ref "U1") (pin "27") (pinfunction "IO2_27") (pintype "bidirectional"))
      (node (ref "U4") (pin "2") (pinfunction "DO(IO1)_2") (pintype "bidirectional"))
    )
    (net (code "20") (name "MOSI") (class "Default")
      (node (ref "D8") (pin "1") (pinfunction "1_1") (pintype "passive"))
      (node (ref "J1") (pin "P3") (pinfunction "CMD_P3") (pintype "bidirectional"))
      (node (ref "J3") (pin "14") (pinfunction "14_14") (pintype "bidirectional"))
      (node (ref "MOSI") (pin "TP") (pinfunction "TP_TP") (pintype "input"))
      (node (ref "R11") (pin "1") (pinfunction "1_1") (pintype "passive"))
      (node (ref "U1") (pin "7") (pinfunction "IO7_7") (pintype "bidirectional"))
      (node (ref "U4") (pin "5") (pinfunction "DI(IO0)_5") (pintype "bidirectional"))
    )
    (net (code "21") (name "Net-(CHG_LED-PadC)") (class "Default")
      (node (ref "CHG_LED") (pin "C") (pinfunction "C_C") (pintype "passive"))
      (node (ref "R1_BAT") (pin "1") (pinfunction "1_1") (pintype "passive"))
    )
    (net (code "22") (name "Net-(D1-CATHODE)") (class "Default")
      (node (ref "C1_BAT1") (pin "1") (pinfunction "1_1") (pintype "passive"))
      (node (ref "D1") (pin "1") (pinfunction "CATHODE_1") (pintype "bidirectional"))
      (node (ref "IC1") (pin "1") (pinfunction "VIN_1") (pintype "bidirectional"))
      (node (ref "IC1") (pin "3") (pinfunction "CE_3") (pintype "bidirectional"))
      (node (ref "Q1") (pin "2") (pinfunction "S_2") (pintype "bidirectional"))
    )
    (net (code "23") (name "Net-(D3-A)") (class "Default")
      (node (ref "C2") (pin "1") (pinfunction "1_1") (pintype "passive"))
      (node (ref "D3") (pin "2") (pinfunction "A_2") (pintype "bidirectional"))
      (node (ref "D4") (pin "1") (pinfunction "K_1") (pintype "bidirectional"))
    )
    (net (code "24") (name "Net-(D6-CATHODE)") (class "Default")
      (node (ref "D6") (pin "1") (pinfunction "CATHODE_1") (pintype "bidirectional"))
      (node (ref "R_CAPACITOR") (pin "1") (pinfunction "1_1") (pintype "passive"))
    )
    (net (code "25") (name "Net-(EPD_C1-Pad2)") (class "Default")
      (node (ref "EPD_C1") (pin "2") (pinfunction "2_2") (pintype "passive"))
      (node (ref "J3") (pin "4") (pinfunction "4_4") (pintype "bidirectional"))
    )
    (net (code "26") (name "Net-(EPD_C2-Pad2)") (class "Default")
      (node (ref "EPD_C2") (pin "2") (pinfunction "2_2") (pintype "passive"))
      (node (ref "J3") (pin "5") (pinfunction "5_5") (pintype "bidirectional"))
    )
    (net (code "27") (name "Net-(EPD_C6-Pad2)") (class "Default")
      (node (ref "EPD_C6") (pin "2") (pinfunction "2_2") (pintype "passive"))
      (node (ref "J3") (pin "18") (pinfunction "18_18") (pintype "bidirectional"))
    )
    (net (code "28") (name "Net-(EPD_C7-Pad2)") (class "Default")
      (node (ref "EPD_C7") (pin "2") (pinfunction "2_2") (pintype "passive"))
      (node (ref "J3") (pin "19") (pinfunction "19_19") (pintype "bidirectional"))
    )
    (net (code "29") (name "Net-(EPD_C8-Pad2)") (class "Default")
      (node (ref "EPD_C8") (pin "2") (pinfunction "2_2") (pintype "passive"))
      (node (ref "J3") (pin "20") (pinfunction "20_20") (pintype "bidirectional"))
    )
    (net (code "30") (name "Net-(EPD_C10-Pad2)") (class "Default")
      (node (ref "EPD_C10") (pin "2") (pinfunction "2_2") (pintype "passive"))
      (node (ref "J3") (pin "22") (pinfunction "22_22") (pintype "bidirectional"))
    )
    (net (code "31") (name "Net-(EPD_C12-Pad2)") (class "Default")
      (node (ref "EPD_C12") (pin "2") (pinfunction "2_2") (pintype "passive"))
      (node (ref "J3") (pin "24") (pinfunction "24_24") (pintype "bidirectional"))
    )
    (net (code "32") (name "Net-(IC2-CT)") (class "Default")
      (node (ref "C_DELAY") (pin "1") (pinfunction "1_1") (pintype "passive"))
      (node (ref "IC2") (pin "5") (pinfunction "CT_5") (pintype "bidirectional"))
    )
    (net (code "33") (name "Net-(J2-PadA5)") (class "Default")
      (node (ref "J2") (pin "A5") (pinfunction "A5_A5") (pintype "bidirectional"))
      (node (ref "R2_USB1") (pin "1") (pinfunction "1_1") (pintype "passive"))
    )
    (net (code "34") (name "Net-(J2-PadB5)") (class "Default")
      (node (ref "J2") (pin "B5") (pinfunction "B5_B5") (pintype "bidirectional"))
      (node (ref "R2_USB") (pin "1") (pinfunction "1_1") (pintype "passive"))
    )
    (net (code "35") (name "Net-(MCP73831-PROG)") (class "Default")
      (node (ref "MCP73831") (pin "5") (pinfunction "PROG_5") (pintype "input"))
      (node (ref "R2_BAT") (pin "2") (pinfunction "2_2") (pintype "passive"))
    )
    (net (code "36") (name "Net-(MCP73831-STAT)") (class "Default")
      (node (ref "MCP73831") (pin "1") (pinfunction "STAT_1") (pintype "output"))
      (node (ref "R1_BAT") (pin "2") (pinfunction "2_2") (pintype "passive"))
    )
    (net (code "37") (name "PREVGH") (class "Default")
      (node (ref "D5") (pin "1") (pinfunction "K_1") (pintype "bidirectional"))
      (node (ref "EPD_C9") (pin "2") (pinfunction "2_2") (pintype "passive"))
      (node (ref "J3") (pin "21") (pinfunction "21_21") (pintype "bidirectional"))
    )
    (net (code "38") (name "PREVGL") (class "Default")
      (node (ref "D4") (pin "2") (pinfunction "A_2") (pintype "bidirectional"))
      (node (ref "EPD_C11") (pin "2") (pinfunction "2_2") (pintype "passive"))
      (node (ref "J3") (pin "23") (pinfunction "23_23") (pintype "bidirectional"))
    )
    (net (code "39") (name "RESE") (class "Default")
      (node (ref "J3") (pin "3") (pinfunction "3_3") (pintype "bidirectional"))
      (node (ref "Q2") (pin "2") (pinfunction "S_2") (pintype "bidirectional"))
      (node (ref "R4") (pin "2") (pinfunction "2_2") (pintype "passive"))
    )
    (net (code "40") (name "RESE'") (class "Default")
      (node (ref "R3") (pin "2") (pinfunction "2_2") (pintype "passive"))
      (node (ref "R4") (pin "1") (pinfunction "1_1") (pintype "passive"))
      (node (ref "SJ1") (pin "2") (pinfunction "2_2") (pintype "passive"))
    )
    (net (code "41") (name "RESET") (class "Default")
      (node (ref "C7") (pin "1") (pinfunction "1_1") (pintype "passive"))
      (node (ref "IC2") (pin "1") (pinfunction "VOUT_1") (pintype "bidirectional"))
      (node (ref "RESET_BUTTON") (pin "3") (pinfunction "3_3") (pintype "passive"))
      (node (ref "RESET_BUTTON") (pin "4") (pinfunction "4_4") (pintype "passive"))
      (node (ref "R_RESET") (pin "1") (pinfunction "1_1") (pintype "passive"))
      (node (ref "U1") (pin "3") (pinfunction "EN_3") (pintype "input"))
    )
    (net (code "42") (name "RTC_RST") (class "Default")
      (node (ref "U1") (pin "16") (pinfunction "IO18_16") (pintype "bidirectional"))
      (node (ref "U3") (pin "4") (pinfunction "~{RST}_4") (pintype "input"))
    )
    (net (code "43") (name "RX") (class "Default")
      (node (ref "RX") (pin "TP") (pinfunction "TP_TP") (pintype "input"))
      (node (ref "U1") (pin "24") (pinfunction "RXD0/GPIO17_24") (pintype "bidirectional"))
    )
    (net (code "44") (name "SCK") (class "Default")
      (node (ref "D9") (pin "1") (pinfunction "1_1") (pintype "passive"))
      (node (ref "J1") (pin "P5") (pinfunction "CLK_P5") (pintype "bidirectional"))
      (node (ref "J3") (pin "13") (pinfunction "13_13") (pintype "bidirectional"))
      (node (ref "R12") (pin "1") (pinfunction "1_1") (pintype "passive"))
      (node (ref "SCK") (pin "TP") (pinfunction "TP_TP") (pintype "input"))
      (node (ref "U1") (pin "6") (pinfunction "IO6_6") (pintype "bidirectional"))
      (node (ref "U4") (pin "6") (pinfunction "CLK_6") (pintype "input"))
    )
    (net (code "45") (name "SCL") (class "Default")
      (node (ref "J4") (pin "4") (pinfunction "4_4") (pintype "passive"))
      (node (ref "R2-PINH") (pin "1") (pinfunction "1_1") (pintype "passive"))
      (node (ref "SENSOR2") (pin "4") (pinfunction "SCK_4") (pintype "input"))
      (node (ref "U1") (pin "20") (pinfunction "IO22_20") (pintype "bidirectional"))
      (node (ref "U2") (pin "7") (pinfunction "SCL_7") (pintype "input"))
      (node (ref "U3") (pin "16") (pinfunction "SCL_16") (pintype "input"))
    )
    (net (code "46") (name "SDA") (class "Default")
      (node (ref "J4") (pin "3") (pinfunction "3_3") (pintype "passive"))
      (node (ref "R1_PINH") (pin "1") (pinfunction "1_1") (pintype "passive"))
      (node (ref "SENSOR2") (pin "3") (pinfunction "SDI_3") (pintype "bidirectional"))
      (node (ref "U1") (pin "19") (pinfunction "IO21_19") (pintype "bidirectional"))
      (node (ref "U2") (pin "8") (pinfunction "SDA_8") (pintype "bidirectional"))
      (node (ref "U3") (pin "15") (pinfunction "SDA_15") (pintype "bidirectional"))
    )
    (net (code "47") (name "SRC") (class "Default")
      (node (ref "C2") (pin "2") (pinfunction "2_2") (pintype "passive"))
      (node (ref "D5") (pin "2") (pinfunction "A_2") (pintype "bidirectional"))
      (node (ref "L1") (pin "1") (pinfunction "1_1") (pintype "passive"))
      (node (ref "Q2") (pin "3") (pinfunction "D_3") (pintype "bidirectional"))
    )
    (net (code "48") (name "SS_SD") (class "Default")
      (node (ref "D12") (pin "1") (pinfunction "1_1") (pintype "passive"))
      (node (ref "J1") (pin "P2") (pinfunction "CD/DAT3_P2") (pintype "bidirectional"))
      (node (ref "R15") (pin "1") (pinfunction "1_1") (pintype "passive"))
      (node (ref "U1") (pin "4") (pinfunction "IO4_4") (pintype "bidirectional"))
    )
    (net (code "49") (name "TX") (class "Default")
      (node (ref "TP1") (pin "TP") (pinfunction "TP_TP") (pintype "input"))
      (node (ref "U1") (pin "25") (pinfunction "TXD0/GPIO16_25") (pintype "bidirectional"))
    )
    (net (code "50") (name "USB_D+") (class "Default")
      (node (ref "D2") (pin "1") (pinfunction "I/O1_1_1") (pintype "bidirectional"))
      (node (ref "U1") (pin "14") (pinfunction "IO13_14") (pintype "bidirectional"))
    )
    (net (code "51") (name "USB_D-") (class "Default")
      (node (ref "D2") (pin "3") (pinfunction "I/O2_1_3") (pintype "bidirectional"))
      (node (ref "U1") (pin "13") (pinfunction "IO12_13") (pintype "bidirectional"))
    )
    (net (code "52") (name "VBAT") (class "Default")
      (node (ref "C2_BAT") (pin "1") (pinfunction "1_1") (pintype "passive"))
      (node (ref "MCP73831") (pin "3") (pinfunction "VBAT_3") (pintype "power_in"))
      (node (ref "Q1") (pin "3") (pinfunction "D_3") (pintype "bidirectional"))
      (node (ref "U2") (pin "2") (pinfunction "CELL_2") (pintype "power_in"))
      (node (ref "U2") (pin "3") (pinfunction "VDD_3") (pintype "power_in"))
      (node (ref "VBAT") (pin "TP") (pinfunction "TP_TP") (pintype "input"))
    )
    (net (code "53") (name "VBUS") (class "Default")
      (node (ref "C1_BAT") (pin "1") (pinfunction "1_1") (pintype "passive"))
      (node (ref "C4_USB") (pin "1") (pinfunction "1_1") (pintype "passive"))
      (node (ref "C5_USB") (pin "1") (pinfunction "1_1") (pintype "passive"))
      (node (ref "CHG_LED") (pin "A") (pinfunction "A_A") (pintype "passive"))
      (node (ref "D1") (pin "2") (pinfunction "ANODE_2") (pintype "bidirectional"))
      (node (ref "D2") (pin "5") (pinfunction "VBUS_5") (pintype "bidirectional"))
      (node (ref "MCP73831") (pin "4") (pinfunction "VIN_4") (pintype "power_in"))
      (node (ref "PFMF.050.1") (pin "2") (pinfunction "2_2") (pintype "passive"))
      (node (ref "Q1") (pin "1") (pinfunction "G_1") (pintype "bidirectional"))
      (node (ref "R1_PWRUSB") (pin "2") (pinfunction "2_2") (pintype "passive"))
      (node (ref "VBUS") (pin "TP") (pinfunction "TP_TP") (pintype "input"))
    )
    (net (code "54") (name "VRTC") (class "Default")
      (node (ref "C10_SUPERCAP") (pin "2") (pinfunction "2_2") (pintype "passive"))
      (node (ref "C11") (pin "1") (pinfunction "1_1") (pintype "passive"))
      (node (ref "R_CAPACITOR") (pin "2") (pinfunction "2_2") (pintype "passive"))
      (node (ref "U3") (pin "14") (pinfunction "VBAT_14") (pintype "power_in"))
    )
    (net (code "55") (name "VUSB") (class "Default")
      (node (ref "J2") (pin "A4") (pinfunction "A4_A4") (pintype "bidirectional"))
      (node (ref "J2") (pin "A9") (pinfunction "A9_A9") (pintype "bidirectional"))
      (node (ref "J2") (pin "B4") (pinfunction "B4_B4") (pintype "bidirectional"))
      (node (ref "J2") (pin "B9") (pinfunction "B9_B9") (pintype "bidirectional"))
      (node (ref "PFMF.050.1") (pin "1") (pinfunction "1_1") (pintype "passive"))
    )
    (net (code "56") (name "unconnected-(IC1-NC-Pad4)") (class "Default")
      (node (ref "IC1") (pin "4") (pinfunction "NC_4") (pintype "no_connect"))
    )
    (net (code "57") (name "unconnected-(IC2-NC-Pad4)") (class "Default")
      (node (ref "IC2") (pin "4") (pinfunction "NC_4") (pintype "no_connect"))
    )
    (net (code "58") (name "unconnected-(J1-DAT1-PadP8)") (class "Default")
      (node (ref "J1") (pin "P8") (pinfunction "DAT1_P8") (pintype "bidirectional"))
    )
    (net (code "59") (name "unconnected-(J1-DAT2-PadP1)") (class "Default")
      (node (ref "J1") (pin "P1") (pinfunction "DAT2_P1") (pintype "bidirectional"))
    )
    (net (code "60") (name "unconnected-(J1-DETECTION_1-PadS1)") (class "Default")
      (node (ref "J1") (pin "S1") (pinfunction "DETECTION_1_S1") (pintype "bidirectional"))
    )
    (net (code "61") (name "unconnected-(J1-DETECTION_2-PadS2)") (class "Default")
      (node (ref "J1") (pin "S2") (pinfunction "DETECTION_2_S2") (pintype "bidirectional"))
    )
    (net (code "62") (name "unconnected-(J2-PadA8)") (class "Default")
      (node (ref "J2") (pin "A8") (pinfunction "A8_A8") (pintype "bidirectional"))
    )
    (net (code "63") (name "unconnected-(J2-PadB8)") (class "Default")
      (node (ref "J2") (pin "B8") (pinfunction "B8_B8") (pintype "bidirectional"))
    )
    (net (code "64") (name "unconnected-(J3-Pad1)") (class "Default")
      (node (ref "J3") (pin "1") (pinfunction "1_1") (pintype "bidirectional"))
    )
    (net (code "65") (name "unconnected-(J3-Pad6)") (class "Default")
      (node (ref "J3") (pin "6") (pinfunction "6_6") (pintype "bidirectional"))
    )
    (net (code "66") (name "unconnected-(J3-Pad7)") (class "Default")
      (node (ref "J3") (pin "7") (pinfunction "7_7") (pintype "bidirectional"))
    )
    (net (code "67") (name "unconnected-(U1-NC-Pad22)") (class "Default")
      (node (ref "U1") (pin "22") (pinfunction "NC_22") (pintype "no_connect"))
    )
    (net (code "68") (name "unconnected-(U2-~{ALERT}-Pad5)") (class "Default")
      (node (ref "U2") (pin "5") (pinfunction "~{ALERT}_5") (pintype "output"))
    )
  )
)
